# M2500X.net
KiCad netlist of a schematic drawn in EAGLE
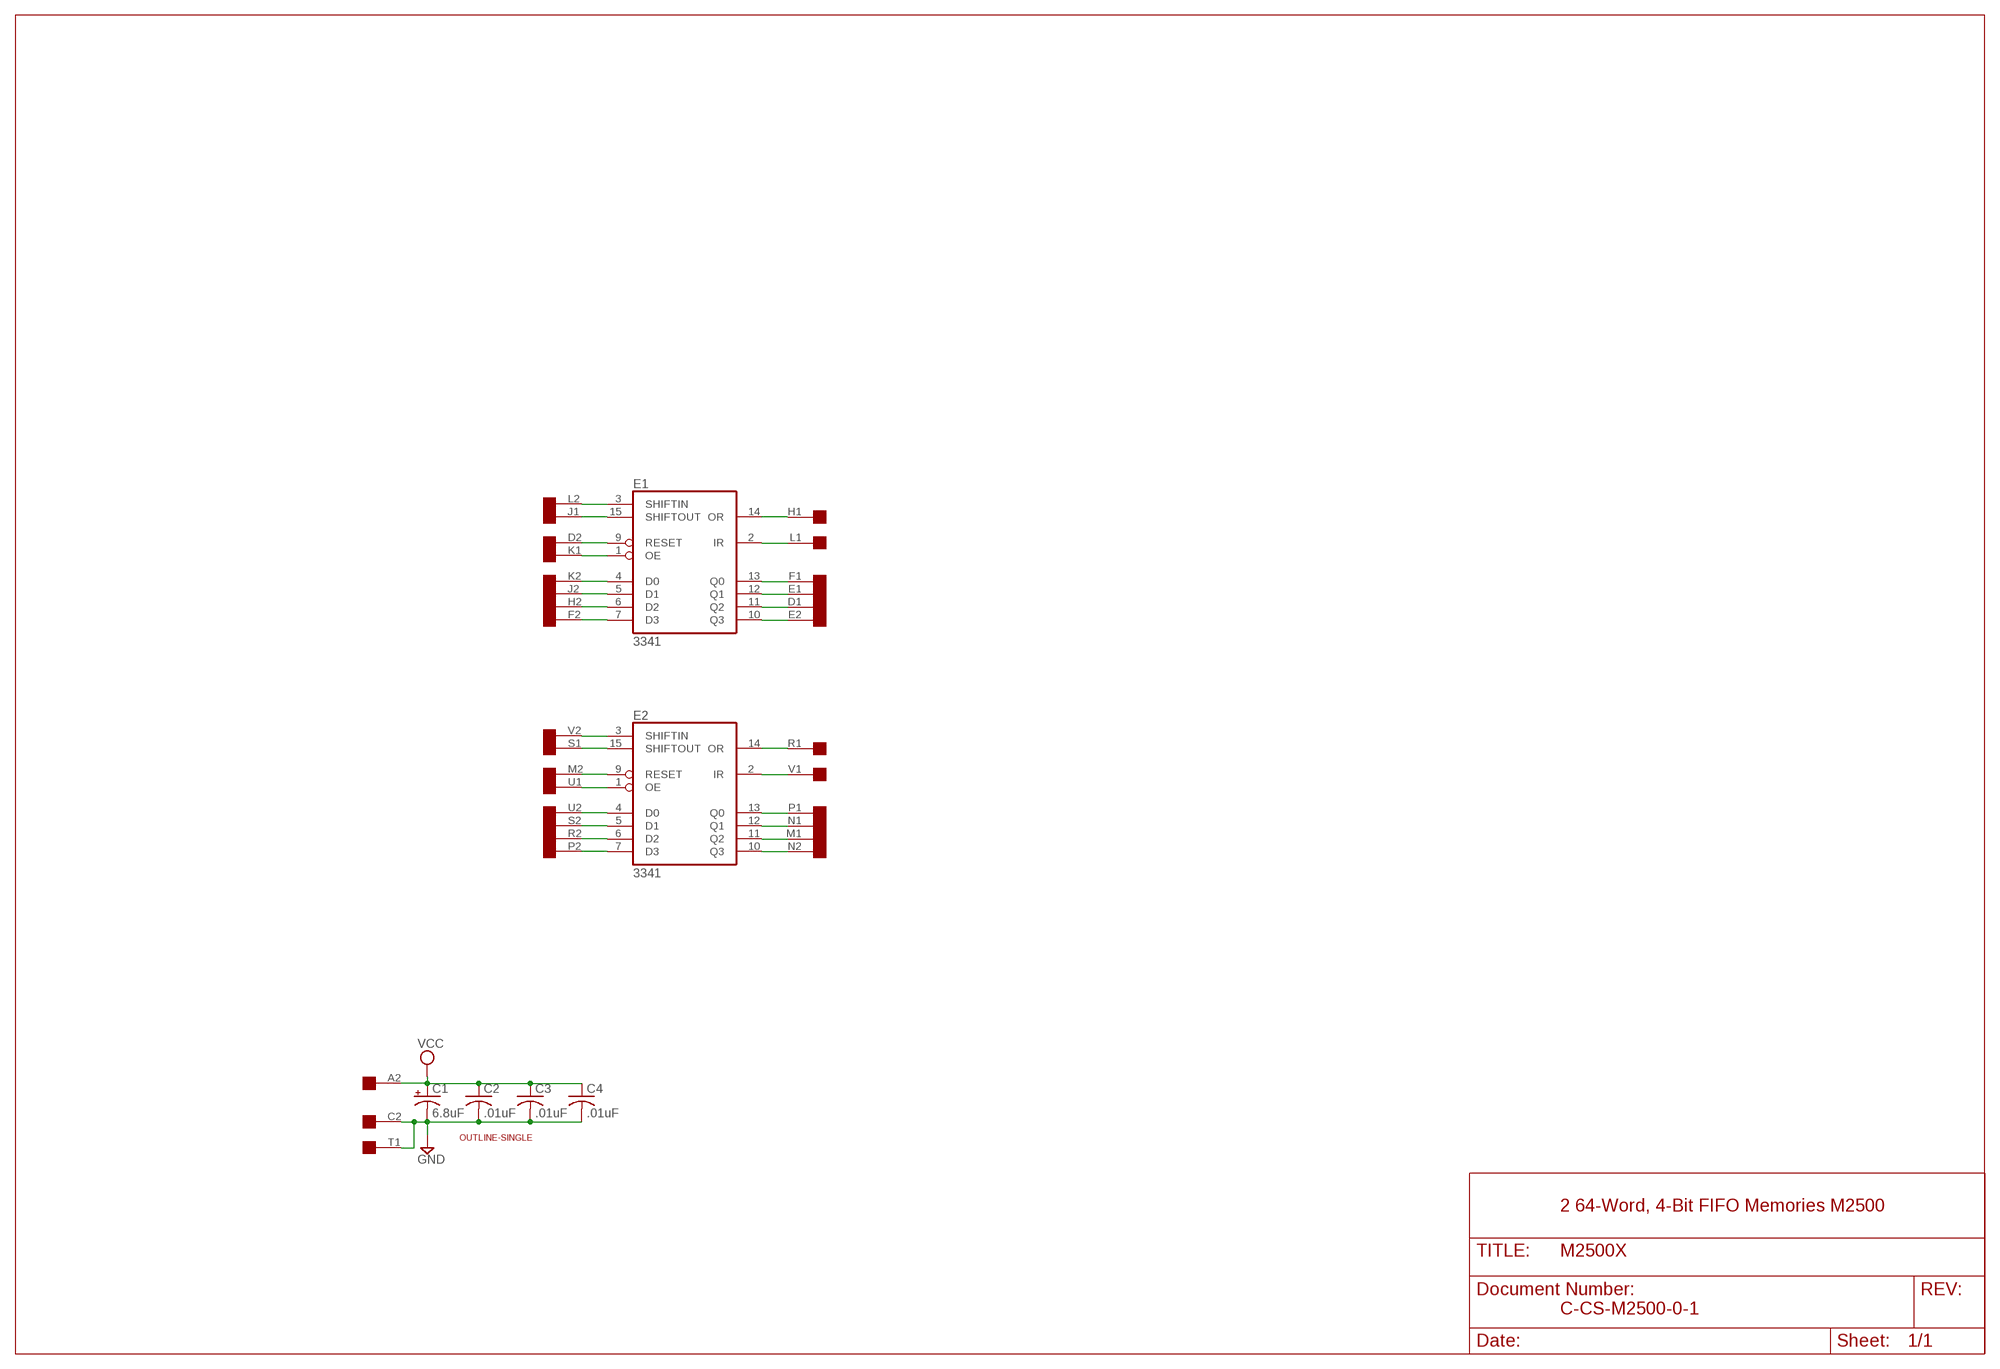
[diagram p0: schematic, sheet 1]

(export (version "E")
  (design (tool "Eeschema 10.0.6"))
  (components
    (comp (ref "C1")
      (value "6.8uF")
      (footprint "eagle-import:E12-8")
      (libsource (lib "eagle-import") (part "CPOL-USE20-8AXIAL"))
    )
    (comp (ref "C2")
      (value ".01uF")
      (footprint "eagle-import:C050-025X075")
      (libsource (lib "eagle-import") (part "C-US050-025X075"))
    )
    (comp (ref "C3")
      (value ".01uF")
      (footprint "eagle-import:C050-025X075")
      (libsource (lib "eagle-import") (part "C-US050-025X075"))
    )
    (comp (ref "C4")
      (value ".01uF")
      (footprint "eagle-import:C050-025X075")
      (libsource (lib "eagle-import") (part "C-US050-025X075"))
    )
    (comp (ref "E1")
      (value "3341")
      (footprint "eagle-import:DIL16")
      (libsource (lib "eagle-import") (part "67C4013"))
    )
    (comp (ref "E2")
      (value "3341")
      (footprint "eagle-import:DIL16")
      (libsource (lib "eagle-import") (part "67C4013"))
    )
    (comp (ref "U$1")
      (value "OUTLINE-SINGLE")
      (footprint "eagle-import:SINGLE")
      (libsource (lib "eagle-import") (part "OUTLINE-SINGLE"))
    )
    (comp (ref "U$2")
      (value "SINGLE")
      (footprint "eagle-import:EDGE-CON2")
      (libsource (lib "eagle-import") (part "SINGLE"))
    )
  )
  (nets
    (net (code "1") (name "GND") (class "Default")
      (node (ref "C1") (pin "-") (pinfunction "-_-") (pintype "passive"))
      (node (ref "C2") (pin "2") (pinfunction "2_2") (pintype "passive"))
      (node (ref "C3") (pin "2") (pinfunction "2_2") (pintype "passive"))
      (node (ref "C4") (pin "2") (pinfunction "2_2") (pintype "passive"))
      (node (ref "U$2") (pin "C2") (pinfunction "1_C2") (pintype "bidirectional"))
      (node (ref "U$2") (pin "T1") (pinfunction "1_T1") (pintype "bidirectional"))
    )
    (net (code "2") (name "Net-(E1A-D0)") (class "Default")
      (node (ref "E1") (pin "4") (pinfunction "D0_4") (pintype "input"))
      (node (ref "U$2") (pin "K2") (pinfunction "1_K2") (pintype "bidirectional"))
    )
    (net (code "3") (name "Net-(E1A-D1)") (class "Default")
      (node (ref "E1") (pin "5") (pinfunction "D1_5") (pintype "input"))
      (node (ref "U$2") (pin "J2") (pinfunction "1_J2") (pintype "bidirectional"))
    )
    (net (code "4") (name "Net-(E1A-D2)") (class "Default")
      (node (ref "E1") (pin "6") (pinfunction "D2_6") (pintype "input"))
      (node (ref "U$2") (pin "H2") (pinfunction "1_H2") (pintype "bidirectional"))
    )
    (net (code "5") (name "Net-(E1A-D3)") (class "Default")
      (node (ref "E1") (pin "7") (pinfunction "D3_7") (pintype "input"))
      (node (ref "U$2") (pin "F2") (pinfunction "1_F2") (pintype "bidirectional"))
    )
    (net (code "6") (name "Net-(E1A-IR)") (class "Default")
      (node (ref "E1") (pin "2") (pinfunction "IR_2") (pintype "output"))
      (node (ref "U$2") (pin "L1") (pinfunction "1_L1") (pintype "bidirectional"))
    )
    (net (code "7") (name "Net-(E1A-OE)") (class "Default")
      (node (ref "E1") (pin "1") (pinfunction "OE_1") (pintype "input"))
      (node (ref "U$2") (pin "K1") (pinfunction "1_K1") (pintype "bidirectional"))
    )
    (net (code "8") (name "Net-(E1A-OR)") (class "Default")
      (node (ref "E1") (pin "14") (pinfunction "OR_14") (pintype "output"))
      (node (ref "U$2") (pin "H1") (pinfunction "1_H1") (pintype "bidirectional"))
    )
    (net (code "9") (name "Net-(E1A-Q0)") (class "Default")
      (node (ref "E1") (pin "13") (pinfunction "Q0_13") (pintype "tri_state"))
      (node (ref "U$2") (pin "F1") (pinfunction "1_F1") (pintype "bidirectional"))
    )
    (net (code "10") (name "Net-(E1A-Q1)") (class "Default")
      (node (ref "E1") (pin "12") (pinfunction "Q1_12") (pintype "tri_state"))
      (node (ref "U$2") (pin "E1") (pinfunction "1_E1") (pintype "bidirectional"))
    )
    (net (code "11") (name "Net-(E1A-Q2)") (class "Default")
      (node (ref "E1") (pin "11") (pinfunction "Q2_11") (pintype "tri_state"))
      (node (ref "U$2") (pin "D1") (pinfunction "1_D1") (pintype "bidirectional"))
    )
    (net (code "12") (name "Net-(E1A-Q3)") (class "Default")
      (node (ref "E1") (pin "10") (pinfunction "Q3_10") (pintype "tri_state"))
      (node (ref "U$2") (pin "E2") (pinfunction "1_E2") (pintype "bidirectional"))
    )
    (net (code "13") (name "Net-(E1A-RESET)") (class "Default")
      (node (ref "E1") (pin "9") (pinfunction "RESET_9") (pintype "input"))
      (node (ref "U$2") (pin "D2") (pinfunction "1_D2") (pintype "bidirectional"))
    )
    (net (code "14") (name "Net-(E1A-SHIFTIN)") (class "Default")
      (node (ref "E1") (pin "3") (pinfunction "SHIFTIN_3") (pintype "input"))
      (node (ref "U$2") (pin "L2") (pinfunction "1_L2") (pintype "bidirectional"))
    )
    (net (code "15") (name "Net-(E1A-SHIFTOUT)") (class "Default")
      (node (ref "E1") (pin "15") (pinfunction "SHIFTOUT_15") (pintype "input"))
      (node (ref "U$2") (pin "J1") (pinfunction "1_J1") (pintype "bidirectional"))
    )
    (net (code "16") (name "Net-(E2A-D0)") (class "Default")
      (node (ref "E2") (pin "4") (pinfunction "D0_4") (pintype "input"))
      (node (ref "U$2") (pin "U2") (pinfunction "1_U2") (pintype "bidirectional"))
    )
    (net (code "17") (name "Net-(E2A-D1)") (class "Default")
      (node (ref "E2") (pin "5") (pinfunction "D1_5") (pintype "input"))
      (node (ref "U$2") (pin "S2") (pinfunction "1_S2") (pintype "bidirectional"))
    )
    (net (code "18") (name "Net-(E2A-D2)") (class "Default")
      (node (ref "E2") (pin "6") (pinfunction "D2_6") (pintype "input"))
      (node (ref "U$2") (pin "R2") (pinfunction "1_R2") (pintype "bidirectional"))
    )
    (net (code "19") (name "Net-(E2A-D3)") (class "Default")
      (node (ref "E2") (pin "7") (pinfunction "D3_7") (pintype "input"))
      (node (ref "U$2") (pin "P2") (pinfunction "1_P2") (pintype "bidirectional"))
    )
    (net (code "20") (name "Net-(E2A-IR)") (class "Default")
      (node (ref "E2") (pin "2") (pinfunction "IR_2") (pintype "output"))
      (node (ref "U$2") (pin "V1") (pinfunction "1_V1") (pintype "bidirectional"))
    )
    (net (code "21") (name "Net-(E2A-OE)") (class "Default")
      (node (ref "E2") (pin "1") (pinfunction "OE_1") (pintype "input"))
      (node (ref "U$2") (pin "U1") (pinfunction "1_U1") (pintype "bidirectional"))
    )
    (net (code "22") (name "Net-(E2A-OR)") (class "Default")
      (node (ref "E2") (pin "14") (pinfunction "OR_14") (pintype "output"))
      (node (ref "U$2") (pin "R1") (pinfunction "1_R1") (pintype "bidirectional"))
    )
    (net (code "23") (name "Net-(E2A-Q0)") (class "Default")
      (node (ref "E2") (pin "13") (pinfunction "Q0_13") (pintype "tri_state"))
      (node (ref "U$2") (pin "P1") (pinfunction "1_P1") (pintype "bidirectional"))
    )
    (net (code "24") (name "Net-(E2A-Q1)") (class "Default")
      (node (ref "E2") (pin "12") (pinfunction "Q1_12") (pintype "tri_state"))
      (node (ref "U$2") (pin "N1") (pinfunction "1_N1") (pintype "bidirectional"))
    )
    (net (code "25") (name "Net-(E2A-Q2)") (class "Default")
      (node (ref "E2") (pin "11") (pinfunction "Q2_11") (pintype "tri_state"))
      (node (ref "U$2") (pin "M1") (pinfunction "1_M1") (pintype "bidirectional"))
    )
    (net (code "26") (name "Net-(E2A-Q3)") (class "Default")
      (node (ref "E2") (pin "10") (pinfunction "Q3_10") (pintype "tri_state"))
      (node (ref "U$2") (pin "N2") (pinfunction "1_N2") (pintype "bidirectional"))
    )
    (net (code "27") (name "Net-(E2A-RESET)") (class "Default")
      (node (ref "E2") (pin "9") (pinfunction "RESET_9") (pintype "input"))
      (node (ref "U$2") (pin "M2") (pinfunction "1_M2") (pintype "bidirectional"))
    )
    (net (code "28") (name "Net-(E2A-SHIFTIN)") (class "Default")
      (node (ref "E2") (pin "3") (pinfunction "SHIFTIN_3") (pintype "input"))
      (node (ref "U$2") (pin "V2") (pinfunction "1_V2") (pintype "bidirectional"))
    )
    (net (code "29") (name "Net-(E2A-SHIFTOUT)") (class "Default")
      (node (ref "E2") (pin "15") (pinfunction "SHIFTOUT_15") (pintype "input"))
      (node (ref "U$2") (pin "S1") (pinfunction "1_S1") (pintype "bidirectional"))
    )
    (net (code "30") (name "VCC") (class "Default")
      (node (ref "C1") (pin "+") (pinfunction "+_+") (pintype "passive"))
      (node (ref "C2") (pin "1") (pinfunction "1_1") (pintype "passive"))
      (node (ref "C3") (pin "1") (pinfunction "1_1") (pintype "passive"))
      (node (ref "C4") (pin "1") (pinfunction "1_1") (pintype "passive"))
      (node (ref "U$2") (pin "A2") (pinfunction "1_A2") (pintype "bidirectional"))
    )
  )
)
